# water_level.net
KiCad netlist of a schematic drawn in EAGLE
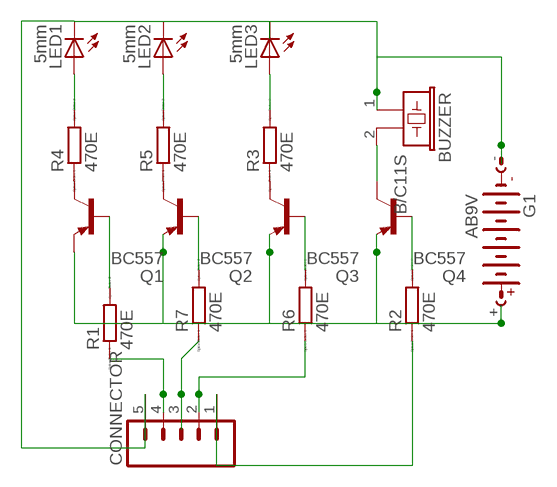
[diagram p0: schematic, sheet 1]

(export (version "E")
  (design (tool "Eeschema 10.0.6"))
  (components
    (comp (ref "BUZZER")
      (value "B/C11S")
      (footprint "eagle-import:B_C11S")
      (libsource (lib "eagle-import") (part "B/C11S"))
    )
    (comp (ref "CONNECTOR")
      (value "M05")
      (footprint "eagle-import:05P")
      (libsource (lib "eagle-import") (part "M05"))
    )
    (comp (ref "G1")
      (value "AB9V")
      (footprint "eagle-import:AB9V")
      (libsource (lib "eagle-import") (part "AB9V"))
    )
    (comp (ref "LED1")
      (value "5mm")
      (footprint "eagle-import:LED5MM")
      (libsource (lib "eagle-import") (part "LED5MM"))
    )
    (comp (ref "LED2")
      (value "5mm")
      (footprint "eagle-import:LED5MM")
      (libsource (lib "eagle-import") (part "LED5MM"))
    )
    (comp (ref "LED3")
      (value "5mm")
      (footprint "eagle-import:LED5MM")
      (libsource (lib "eagle-import") (part "LED5MM"))
    )
    (comp (ref "Q1")
      (value "BC557")
      (footprint "eagle-import:TO92")
      (libsource (lib "eagle-import") (part "BC557"))
    )
    (comp (ref "Q2")
      (value "BC557")
      (footprint "eagle-import:TO92")
      (libsource (lib "eagle-import") (part "BC557"))
    )
    (comp (ref "Q3")
      (value "BC557")
      (footprint "eagle-import:TO92")
      (libsource (lib "eagle-import") (part "BC557"))
    )
    (comp (ref "Q4")
      (value "BC557")
      (footprint "eagle-import:TO92")
      (libsource (lib "eagle-import") (part "BC557"))
    )
    (comp (ref "R1")
      (value "470E")
      (footprint "eagle-import:0204_7")
      (libsource (lib "eagle-import") (part "R0204/7"))
    )
    (comp (ref "R2")
      (value "470E")
      (footprint "eagle-import:0204_7")
      (libsource (lib "eagle-import") (part "R0204/7"))
    )
    (comp (ref "R3")
      (value "470E")
      (footprint "eagle-import:0204_7")
      (libsource (lib "eagle-import") (part "R0204/7"))
    )
    (comp (ref "R4")
      (value "470E")
      (footprint "eagle-import:0204_7")
      (libsource (lib "eagle-import") (part "R0204/7"))
    )
    (comp (ref "R5")
      (value "470E")
      (footprint "eagle-import:0204_7")
      (libsource (lib "eagle-import") (part "R0204/7"))
    )
    (comp (ref "R6")
      (value "470E")
      (footprint "eagle-import:0204_7")
      (libsource (lib "eagle-import") (part "R0204/7"))
    )
    (comp (ref "R7")
      (value "470E")
      (footprint "eagle-import:0204_7")
      (libsource (lib "eagle-import") (part "R0204/7"))
    )
  )
  (nets
    (net (code "1") (name "Net-(CONNECTOR-Pad1)") (class "Default")
      (node (ref "CONNECTOR") (pin "1") (pinfunction "1_1") (pintype "passive"))
      (node (ref "R2") (pin "1") (pinfunction "1_1") (pintype "passive"))
    )
    (net (code "2") (name "Net-(CONNECTOR-Pad2)") (class "Default")
      (node (ref "CONNECTOR") (pin "2") (pinfunction "2_2") (pintype "passive"))
      (node (ref "R6") (pin "1") (pinfunction "1_1") (pintype "passive"))
    )
    (net (code "3") (name "Net-(CONNECTOR-Pad3)") (class "Default")
      (node (ref "CONNECTOR") (pin "3") (pinfunction "3_3") (pintype "passive"))
      (node (ref "R7") (pin "1") (pinfunction "1_1") (pintype "passive"))
    )
    (net (code "4") (name "Net-(CONNECTOR-Pad4)") (class "Default")
      (node (ref "CONNECTOR") (pin "4") (pinfunction "4_4") (pintype "passive"))
      (node (ref "R1") (pin "1") (pinfunction "1_1") (pintype "passive"))
    )
    (net (code "5") (name "Net-(LED1-C)") (class "Default")
      (node (ref "BUZZER") (pin "1") (pinfunction "1_1") (pintype "passive"))
      (node (ref "CONNECTOR") (pin "5") (pinfunction "5_5") (pintype "passive"))
      (node (ref "G1") (pin "-") (pinfunction "-_-") (pintype "passive"))
      (node (ref "LED1") (pin "K") (pinfunction "C_K") (pintype "passive"))
      (node (ref "LED2") (pin "K") (pinfunction "C_K") (pintype "passive"))
      (node (ref "LED3") (pin "K") (pinfunction "C_K") (pintype "passive"))
    )
    (net (code "6") (name "Net-(LED1-PadA)") (class "Default")
      (node (ref "LED1") (pin "A") (pinfunction "A_A") (pintype "passive"))
      (node (ref "R4") (pin "2") (pinfunction "2_2") (pintype "passive"))
    )
    (net (code "7") (name "Net-(LED2-PadA)") (class "Default")
      (node (ref "LED2") (pin "A") (pinfunction "A_A") (pintype "passive"))
      (node (ref "R5") (pin "2") (pinfunction "2_2") (pintype "passive"))
    )
    (net (code "8") (name "Net-(LED3-PadA)") (class "Default")
      (node (ref "LED3") (pin "A") (pinfunction "A_A") (pintype "passive"))
      (node (ref "R3") (pin "2") (pinfunction "2_2") (pintype "passive"))
    )
    (net (code "9") (name "Net-(Q1-B)") (class "Default")
      (node (ref "Q1") (pin "2") (pinfunction "B_2") (pintype "passive"))
      (node (ref "R1") (pin "2") (pinfunction "2_2") (pintype "passive"))
    )
    (net (code "10") (name "Net-(Q1-C)") (class "Default")
      (node (ref "Q1") (pin "3") (pinfunction "C_3") (pintype "passive"))
      (node (ref "R4") (pin "1") (pinfunction "1_1") (pintype "passive"))
    )
    (net (code "11") (name "Net-(Q1-E)") (class "Default")
      (node (ref "G1") (pin "+") (pinfunction "+_+") (pintype "passive"))
      (node (ref "Q1") (pin "1") (pinfunction "E_1") (pintype "passive"))
      (node (ref "Q2") (pin "1") (pinfunction "E_1") (pintype "passive"))
      (node (ref "Q3") (pin "1") (pinfunction "E_1") (pintype "passive"))
      (node (ref "Q4") (pin "1") (pinfunction "E_1") (pintype "passive"))
    )
    (net (code "12") (name "Net-(Q2-B)") (class "Default")
      (node (ref "Q2") (pin "2") (pinfunction "B_2") (pintype "passive"))
      (node (ref "R7") (pin "2") (pinfunction "2_2") (pintype "passive"))
    )
    (net (code "13") (name "Net-(Q2-C)") (class "Default")
      (node (ref "Q2") (pin "3") (pinfunction "C_3") (pintype "passive"))
      (node (ref "R5") (pin "1") (pinfunction "1_1") (pintype "passive"))
    )
    (net (code "14") (name "Net-(Q3-B)") (class "Default")
      (node (ref "Q3") (pin "2") (pinfunction "B_2") (pintype "passive"))
      (node (ref "R6") (pin "2") (pinfunction "2_2") (pintype "passive"))
    )
    (net (code "15") (name "Net-(Q3-C)") (class "Default")
      (node (ref "Q3") (pin "3") (pinfunction "C_3") (pintype "passive"))
      (node (ref "R3") (pin "1") (pinfunction "1_1") (pintype "passive"))
    )
    (net (code "16") (name "Net-(Q4-B)") (class "Default")
      (node (ref "Q4") (pin "2") (pinfunction "B_2") (pintype "passive"))
      (node (ref "R2") (pin "2") (pinfunction "2_2") (pintype "passive"))
    )
    (net (code "17") (name "Net-(Q4-C)") (class "Default")
      (node (ref "BUZZER") (pin "2") (pinfunction "2_2") (pintype "passive"))
      (node (ref "Q4") (pin "3") (pinfunction "C_3") (pintype "passive"))
    )
  )
)
